# MCU_RGB.net
KiCad netlist of a schematic drawn in Altium Designer
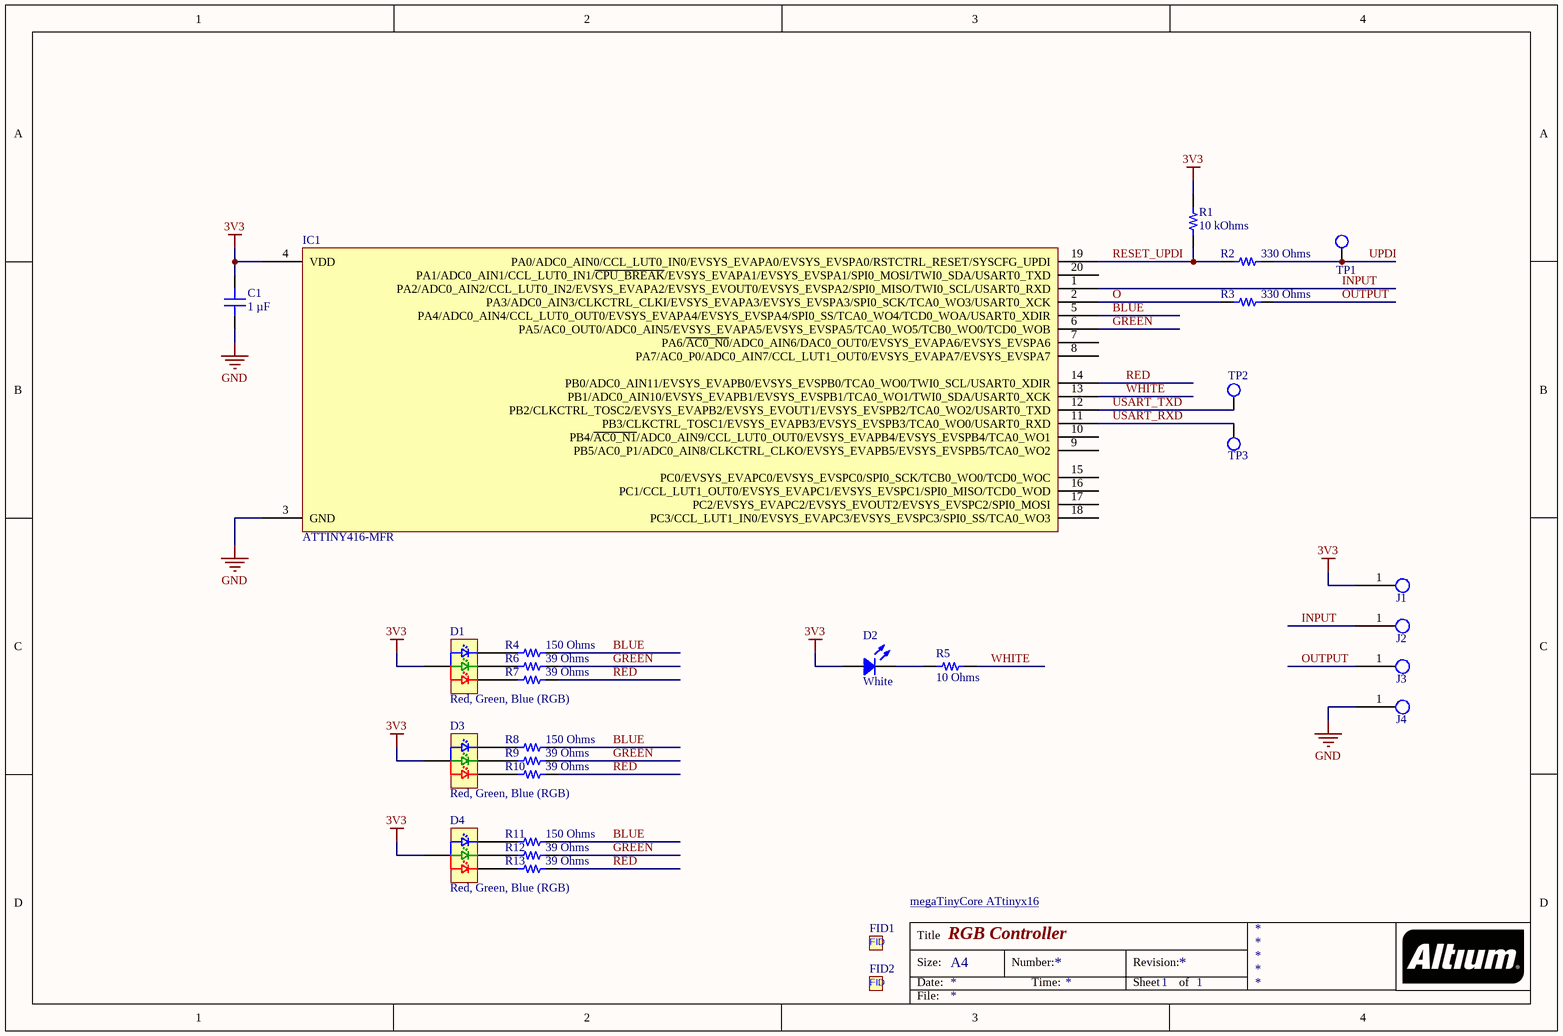
[diagram p0: MCU RGB.SchDoc]

(export (version "E")
  (design (tool "Eeschema 10.0.6"))
  (components
    (comp (ref "C1")
      (value "1 µF")
      (footprint "CAP 0603_1608")
      (description "CAP CER 1UF 25V X7R 0603")
      (fields
        (field (name "PART NUMBER") "GCM188R71E105KA64D")
        (field (name "MANUFACTURER") "Murata Electronics")
      )
      (libsource (lib "altiumlibrary.com") (part "Capacitor"))
    )
    (comp (ref "D1")
      (value "Red, Green, Blue (RGB)")
      (footprint "Harvatek B38G3RGB-10D0003H2U1930")
      (description "LED RGB MIXED WHITE ( 1.6(L)X1.6")
      (fields
        (field (name "PART NUMBER") "B38G3RGB-10D0003H2U1930")
        (field (name "MANUFACTURER") "Harvatek Corporation")
      )
      (libsource (lib "altiumlibrary.com") (part "Harvatek B38G3RGB-10D0003H2U1930"))
    )
    (comp (ref "D2")
      (value "White")
      (footprint "LED 0603_1608")
      (description "1.6(L)X0.8(W)X0.4(H) MM WHITE LE")
      (fields
        (field (name "PART NUMBER") "B1931TW--20P000314U1930")
        (field (name "MANUFACTURER") "Harvatek Corporation")
      )
      (libsource (lib "altiumlibrary.com") (part "LED"))
    )
    (comp (ref "D3")
      (value "Red, Green, Blue (RGB)")
      (footprint "Harvatek B38G3RGB-10D0003H2U1930")
      (description "LED RGB MIXED WHITE ( 1.6(L)X1.6")
      (fields
        (field (name "PART NUMBER") "B38G3RGB-10D0003H2U1930")
        (field (name "MANUFACTURER") "Harvatek Corporation")
      )
      (libsource (lib "altiumlibrary.com") (part "Harvatek B38G3RGB-10D0003H2U1930"))
    )
    (comp (ref "D4")
      (value "Red, Green, Blue (RGB)")
      (footprint "Harvatek B38G3RGB-10D0003H2U1930")
      (description "LED RGB MIXED WHITE ( 1.6(L)X1.6")
      (fields
        (field (name "PART NUMBER") "B38G3RGB-10D0003H2U1930")
        (field (name "MANUFACTURER") "Harvatek Corporation")
      )
      (libsource (lib "altiumlibrary.com") (part "Harvatek B38G3RGB-10D0003H2U1930"))
    )
    (comp (ref "FID1")
      (value "Fiducial")
      (footprint "Fiducial-1mm")
      (libsource (lib "Original Circuit") (part "Fiducial"))
    )
    (comp (ref "FID2")
      (value "Fiducial")
      (footprint "Fiducial-1mm")
      (libsource (lib "Original Circuit") (part "Fiducial"))
    )
    (comp (ref "IC1")
      (value "ATTINY416-MFR")
      (footprint "MICROCHIP VQFN-20 3X3 REB")
      (description "IC MCU 8BIT 4KB FLASH 20VQFN")
      (fields (field (name "MANUFACTURER") "Microchip Technology"))
      (libsource (lib "altiumlibrary.com") (part "MICROCHIP ATTINY416-MFR VQFN20"))
    )
    (comp (ref "J1")
      (value "e-tex pad")
      (footprint "MFR PARTNO")
      (libsource (lib "e-tex pad") (part "e-tex pad"))
    )
    (comp (ref "J2")
      (value "e-tex pad")
      (footprint "MFR PARTNO")
      (libsource (lib "e-tex pad") (part "e-tex pad"))
    )
    (comp (ref "J3")
      (value "e-tex pad")
      (footprint "MFR PARTNO")
      (libsource (lib "e-tex pad") (part "e-tex pad"))
    )
    (comp (ref "J4")
      (value "e-tex pad")
      (footprint "MFR PARTNO")
      (libsource (lib "e-tex pad") (part "e-tex pad"))
    )
    (comp (ref "R1")
      (value "10 kOhms")
      (footprint "RES 0201_0603")
      (description "RES SMD 10K OHM 5% 1/20W 0201")
      (fields (field (name "PART NUMBER") "CR0201-JW-103GLF") (field (name "MANUFACTURER") "Bourns Inc."))
      (libsource (lib "altiumlibrary.com") (part "Resistor"))
    )
    (comp (ref "R2")
      (value "330 Ohms")
      (footprint "RES 0201_0603")
      (description "RES 330 OHM 1% 1/20W 0201")
      (fields
        (field (name "PART NUMBER") "WR02X3300FAL")
        (field (name "MANUFACTURER") "Walsin Technology Corporation")
      )
      (libsource (lib "altiumlibrary.com") (part "Resistor"))
    )
    (comp (ref "R3")
      (value "330 Ohms")
      (footprint "RES 0201_0603")
      (description "RES 330 OHM 1% 1/20W 0201")
      (fields
        (field (name "PART NUMBER") "WR02X3300FAL")
        (field (name "MANUFACTURER") "Walsin Technology Corporation")
      )
      (libsource (lib "altiumlibrary.com") (part "Resistor"))
    )
    (comp (ref "R4")
      (value "150 Ohms")
      (footprint "RES 0201_0603")
      (description "RES 150 OHM 5% 1/20W 0201")
      (fields
        (field (name "PART NUMBER") "WR02X151 JAL")
        (field (name "MANUFACTURER") "Walsin Technology Corporation")
      )
      (libsource (lib "altiumlibrary.com") (part "Resistor"))
    )
    (comp (ref "R5")
      (value "10 Ohms")
      (footprint "RES 0201_0603")
      (description "RES 10 OHM 1% 1/20W 0201")
      (fields
        (field (name "PART NUMBER") "WR02X10R0FAL")
        (field (name "MANUFACTURER") "Walsin Technology Corporation")
      )
      (libsource (lib "altiumlibrary.com") (part "Resistor"))
    )
    (comp (ref "R6")
      (value "39 Ohms")
      (footprint "RES 0201_0603")
      (description "RES SMD 39 OHM 5% 1/20W 0201")
      (fields (field (name "PART NUMBER") "CR0201-JW-390GLF") (field (name "MANUFACTURER") "Bourns Inc."))
      (libsource (lib "altiumlibrary.com") (part "Resistor"))
    )
    (comp (ref "R7")
      (value "39 Ohms")
      (footprint "RES 0201_0603")
      (description "RES SMD 39 OHM 5% 1/20W 0201")
      (fields (field (name "PART NUMBER") "CR0201-JW-390GLF") (field (name "MANUFACTURER") "Bourns Inc."))
      (libsource (lib "altiumlibrary.com") (part "Resistor"))
    )
    (comp (ref "R8")
      (value "150 Ohms")
      (footprint "RES 0201_0603")
      (description "RES 150 OHM 5% 1/20W 0201")
      (fields
        (field (name "PART NUMBER") "WR02X151 JAL")
        (field (name "MANUFACTURER") "Walsin Technology Corporation")
      )
      (libsource (lib "altiumlibrary.com") (part "Resistor"))
    )
    (comp (ref "R9")
      (value "39 Ohms")
      (footprint "RES 0201_0603")
      (description "RES SMD 39 OHM 5% 1/20W 0201")
      (fields (field (name "PART NUMBER") "CR0201-JW-390GLF") (field (name "MANUFACTURER") "Bourns Inc."))
      (libsource (lib "altiumlibrary.com") (part "Resistor"))
    )
    (comp (ref "R10")
      (value "39 Ohms")
      (footprint "RES 0201_0603")
      (description "RES SMD 39 OHM 5% 1/20W 0201")
      (fields (field (name "PART NUMBER") "CR0201-JW-390GLF") (field (name "MANUFACTURER") "Bourns Inc."))
      (libsource (lib "altiumlibrary.com") (part "Resistor"))
    )
    (comp (ref "R11")
      (value "150 Ohms")
      (footprint "RES 0201_0603")
      (description "RES 150 OHM 5% 1/20W 0201")
      (fields
        (field (name "PART NUMBER") "WR02X151 JAL")
        (field (name "MANUFACTURER") "Walsin Technology Corporation")
      )
      (libsource (lib "altiumlibrary.com") (part "Resistor"))
    )
    (comp (ref "R12")
      (value "39 Ohms")
      (footprint "RES 0201_0603")
      (description "RES SMD 39 OHM 5% 1/20W 0201")
      (fields (field (name "PART NUMBER") "CR0201-JW-390GLF") (field (name "MANUFACTURER") "Bourns Inc."))
      (libsource (lib "altiumlibrary.com") (part "Resistor"))
    )
    (comp (ref "R13")
      (value "39 Ohms")
      (footprint "RES 0201_0603")
      (description "RES SMD 39 OHM 5% 1/20W 0201")
      (fields (field (name "PART NUMBER") "CR0201-JW-390GLF") (field (name "MANUFACTURER") "Bourns Inc."))
      (libsource (lib "altiumlibrary.com") (part "Resistor"))
    )
    (comp (ref "TP1")
      (value "Test Point")
      (footprint "TestPoint-1.5mm")
      (libsource (lib "Original Circuit") (part "Test Point"))
    )
    (comp (ref "TP2")
      (value "Test Point")
      (footprint "TestPoint-1.5mm")
      (libsource (lib "Original Circuit") (part "Test Point"))
    )
    (comp (ref "TP3")
      (value "Test Point")
      (footprint "TestPoint-1.5mm")
      (libsource (lib "Original Circuit") (part "Test Point"))
    )
  )
  (nets
    (net (code "1") (name "/BLUE") (class "Default")
      (node (ref "IC1") (pin "5") (pinfunction "PA4/ADC0_AIN4/CCL_LUT0_OUT0/EVSYS_EVAPA4/EVSYS_EVSPA4/SPI0_SS/TCA0_WO4/TCD0_WOA/USART0_XDIR_5") (pintype "passive"))
      (node (ref "R11") (pin "2") (pinfunction "2_2") (pintype "passive"))
      (node (ref "R4") (pin "2") (pinfunction "2_2") (pintype "passive"))
      (node (ref "R8") (pin "2") (pinfunction "2_2") (pintype "passive"))
    )
    (net (code "2") (name "/GREEN") (class "Default")
      (node (ref "IC1") (pin "6") (pinfunction "PA5/AC0_OUT0/ADC0_AIN5/EVSYS_EVAPA5/EVSYS_EVSPA5/TCA0_WO5/TCB0_WO0/TCD0_WOB_6") (pintype "passive"))
      (node (ref "R12") (pin "2") (pinfunction "2_2") (pintype "passive"))
      (node (ref "R6") (pin "2") (pinfunction "2_2") (pintype "passive"))
      (node (ref "R9") (pin "2") (pinfunction "2_2") (pintype "passive"))
    )
    (net (code "3") (name "/INPUT") (class "Default")
      (node (ref "IC1") (pin "1") (pinfunction "PA2/ADC0_AIN2/CCL_LUT0_IN2/EVSYS_EVAPA2/EVSYS_EVOUT0/EVSYS_EVSPA2/SPI0_MISO/TWI0_SCL/USART0_RXD_1") (pintype "passive"))
      (node (ref "J2") (pin "1") (pinfunction "ETEXTILE_1") (pintype "passive"))
    )
    (net (code "4") (name "/O") (class "Default")
      (node (ref "IC1") (pin "2") (pinfunction "PA3/ADC0_AIN3/CLKCTRL_CLKI/EVSYS_EVAPA3/EVSYS_EVSPA3/SPI0_SCK/TCA0_WO3/USART0_XCK_2") (pintype "passive"))
      (node (ref "R3") (pin "1") (pinfunction "1_1") (pintype "passive"))
    )
    (net (code "5") (name "/OUTPUT") (class "Default")
      (node (ref "J3") (pin "1") (pinfunction "ETEXTILE_1") (pintype "passive"))
      (node (ref "R3") (pin "2") (pinfunction "2_2") (pintype "passive"))
    )
    (net (code "6") (name "/RED") (class "Default")
      (node (ref "IC1") (pin "14") (pinfunction "PB0/ADC0_AIN11/EVSYS_EVAPB0/EVSYS_EVSPB0/TCA0_WO0/TWI0_SCL/USART0_XDIR_14") (pintype "passive"))
      (node (ref "R10") (pin "2") (pinfunction "2_2") (pintype "passive"))
      (node (ref "R13") (pin "2") (pinfunction "2_2") (pintype "passive"))
      (node (ref "R7") (pin "2") (pinfunction "2_2") (pintype "passive"))
    )
    (net (code "7") (name "/RESET_UPDI") (class "Default")
      (node (ref "IC1") (pin "19") (pinfunction "PA0/ADC0_AIN0/CCL_LUT0_IN0/EVSYS_EVAPA0/EVSYS_EVSPA0/RSTCTRL_RESET/SYSCFG_UPDI_19") (pintype "passive"))
      (node (ref "R1") (pin "1") (pinfunction "1_1") (pintype "passive"))
      (node (ref "R2") (pin "1") (pinfunction "1_1") (pintype "passive"))
    )
    (net (code "8") (name "/UPDI") (class "Default")
      (node (ref "R2") (pin "2") (pinfunction "2_2") (pintype "passive"))
      (node (ref "TP1") (pin "1") (pinfunction "TP_1") (pintype "passive"))
    )
    (net (code "9") (name "/USART_RXD") (class "Default")
      (node (ref "IC1") (pin "11") (pinfunction "PB3/CLKCTRL_TOSC1/EVSYS_EVAPB3/EVSYS_EVSPB3/TCA0_WO0/USART0_RXD_11") (pintype "passive"))
      (node (ref "TP3") (pin "1") (pinfunction "TP_1") (pintype "passive"))
    )
    (net (code "10") (name "/USART_TXD") (class "Default")
      (node (ref "IC1") (pin "12") (pinfunction "PB2/CLKCTRL_TOSC2/EVSYS_EVAPB2/EVSYS_EVOUT1/EVSYS_EVSPB2/TCA0_WO2/USART0_TXD_12") (pintype "passive"))
      (node (ref "TP2") (pin "1") (pinfunction "TP_1") (pintype "passive"))
    )
    (net (code "11") (name "/WHITE") (class "Default")
      (node (ref "IC1") (pin "13") (pinfunction "PB1/ADC0_AIN10/EVSYS_EVAPB1/EVSYS_EVSPB1/TCA0_WO1/TWI0_SDA/USART0_XCK_13") (pintype "passive"))
      (node (ref "R5") (pin "2") (pinfunction "2_2") (pintype "passive"))
    )
    (net (code "12") (name "3V3") (class "Default")
      (node (ref "C1") (pin "2") (pinfunction "2_2") (pintype "passive"))
      (node (ref "D1") (pin "3") (pinfunction "ANODE_3") (pintype "passive"))
      (node (ref "D2") (pin "1") (pinfunction "1_1") (pintype "passive"))
      (node (ref "D3") (pin "3") (pinfunction "ANODE_3") (pintype "passive"))
      (node (ref "D4") (pin "3") (pinfunction "ANODE_3") (pintype "passive"))
      (node (ref "IC1") (pin "4") (pinfunction "VDD_4") (pintype "passive"))
      (node (ref "J1") (pin "1") (pinfunction "ETEXTILE_1") (pintype "passive"))
      (node (ref "R1") (pin "2") (pinfunction "2_2") (pintype "passive"))
    )
    (net (code "13") (name "GND") (class "Default")
      (node (ref "C1") (pin "1") (pinfunction "1_1") (pintype "passive"))
      (node (ref "IC1") (pin "3") (pinfunction "GND_3") (pintype "passive"))
      (node (ref "J4") (pin "1") (pinfunction "ETEXTILE_1") (pintype "passive"))
    )
    (net (code "14") (name "Net-(D1-BLUE)") (class "Default")
      (node (ref "D1") (pin "2") (pinfunction "BLUE_2") (pintype "passive"))
      (node (ref "R4") (pin "1") (pinfunction "1_1") (pintype "passive"))
    )
    (net (code "15") (name "Net-(D1-GREEN)") (class "Default")
      (node (ref "D1") (pin "1") (pinfunction "GREEN_1") (pintype "passive"))
      (node (ref "R6") (pin "1") (pinfunction "1_1") (pintype "passive"))
    )
    (net (code "16") (name "Net-(D1-RED)") (class "Default")
      (node (ref "D1") (pin "4") (pinfunction "RED_4") (pintype "passive"))
      (node (ref "R7") (pin "1") (pinfunction "1_1") (pintype "passive"))
    )
    (net (code "17") (name "Net-(D2-Pad2)") (class "Default")
      (node (ref "D2") (pin "2") (pinfunction "2_2") (pintype "passive"))
      (node (ref "R5") (pin "1") (pinfunction "1_1") (pintype "passive"))
    )
    (net (code "18") (name "Net-(D3-BLUE)") (class "Default")
      (node (ref "D3") (pin "2") (pinfunction "BLUE_2") (pintype "passive"))
      (node (ref "R8") (pin "1") (pinfunction "1_1") (pintype "passive"))
    )
    (net (code "19") (name "Net-(D3-GREEN)") (class "Default")
      (node (ref "D3") (pin "1") (pinfunction "GREEN_1") (pintype "passive"))
      (node (ref "R9") (pin "1") (pinfunction "1_1") (pintype "passive"))
    )
    (net (code "20") (name "Net-(D3-RED)") (class "Default")
      (node (ref "D3") (pin "4") (pinfunction "RED_4") (pintype "passive"))
      (node (ref "R10") (pin "1") (pinfunction "1_1") (pintype "passive"))
    )
    (net (code "21") (name "Net-(D4-BLUE)") (class "Default")
      (node (ref "D4") (pin "2") (pinfunction "BLUE_2") (pintype "passive"))
      (node (ref "R11") (pin "1") (pinfunction "1_1") (pintype "passive"))
    )
    (net (code "22") (name "Net-(D4-GREEN)") (class "Default")
      (node (ref "D4") (pin "1") (pinfunction "GREEN_1") (pintype "passive"))
      (node (ref "R12") (pin "1") (pinfunction "1_1") (pintype "passive"))
    )
    (net (code "23") (name "Net-(D4-RED)") (class "Default")
      (node (ref "D4") (pin "4") (pinfunction "RED_4") (pintype "passive"))
      (node (ref "R13") (pin "1") (pinfunction "1_1") (pintype "passive"))
    )
    (net (code "24") (name "unconnected-(IC1-PA1{slash}ADC0_AIN1{slash}CCL_LUT0_IN1{slash}~{CPU_BREAK}{slash}EVSYS_EVAPA1{slash}EVSYS_EVSPA1{slash}SPI0_MOSI{slash}TWI0_SDA{slash}USART0_TXD-Pad20)") (class "Default")
      (node (ref "IC1") (pin "20") (pinfunction "PA1/ADC0_AIN1/CCL_LUT0_IN1/~{CPU_BREAK}/EVSYS_EVAPA1/EVSYS_EVSPA1/SPI0_MOSI/TWI0_SDA/USART0_TXD_20") (pintype "passive"))
    )
    (net (code "25") (name "unconnected-(IC1-PA6{slash}~{AC0_N0}{slash}ADC0_AIN6{slash}DAC0_OUT0{slash}EVSYS_EVAPA6{slash}EVSYS_EVSPA6-Pad7)") (class "Default")
      (node (ref "IC1") (pin "7") (pinfunction "PA6/~{AC0_N0}/ADC0_AIN6/DAC0_OUT0/EVSYS_EVAPA6/EVSYS_EVSPA6_7") (pintype "passive"))
    )
    (net (code "26") (name "unconnected-(IC1-PA7{slash}AC0_P0{slash}ADC0_AIN7{slash}CCL_LUT1_OUT0{slash}EVSYS_EVAPA7{slash}EVSYS_EVSPA7-Pad8)") (class "Default")
      (node (ref "IC1") (pin "8") (pinfunction "PA7/AC0_P0/ADC0_AIN7/CCL_LUT1_OUT0/EVSYS_EVAPA7/EVSYS_EVSPA7_8") (pintype "passive"))
    )
    (net (code "27") (name "unconnected-(IC1-PB4{slash}~{AC0_N1}{slash}ADC0_AIN9{slash}CCL_LUT0_OUT0{slash}EVSYS_EVAPB4{slash}EVSYS_EVSPB4{slash}TCA0_WO1-Pad10)") (class "Default")
      (node (ref "IC1") (pin "10") (pinfunction "PB4/~{AC0_N1}/ADC0_AIN9/CCL_LUT0_OUT0/EVSYS_EVAPB4/EVSYS_EVSPB4/TCA0_WO1_10") (pintype "passive"))
    )
    (net (code "28") (name "unconnected-(IC1-PB5{slash}AC0_P1{slash}ADC0_AIN8{slash}CLKCTRL_CLKO{slash}EVSYS_EVAPB5{slash}EVSYS_EVSPB5{slash}TCA0_WO2-Pad9)") (class "Default")
      (node (ref "IC1") (pin "9") (pinfunction "PB5/AC0_P1/ADC0_AIN8/CLKCTRL_CLKO/EVSYS_EVAPB5/EVSYS_EVSPB5/TCA0_WO2_9") (pintype "passive"))
    )
    (net (code "29") (name "unconnected-(IC1-PC0{slash}EVSYS_EVAPC0{slash}EVSYS_EVSPC0{slash}SPI0_SCK{slash}TCB0_WO0{slash}TCD0_WOC-Pad15)") (class "Default")
      (node (ref "IC1") (pin "15") (pinfunction "PC0/EVSYS_EVAPC0/EVSYS_EVSPC0/SPI0_SCK/TCB0_WO0/TCD0_WOC_15") (pintype "passive"))
    )
    (net (code "30") (name "unconnected-(IC1-PC1{slash}CCL_LUT1_OUT0{slash}EVSYS_EVAPC1{slash}EVSYS_EVSPC1{slash}SPI0_MISO{slash}TCD0_WOD-Pad16)") (class "Default")
      (node (ref "IC1") (pin "16") (pinfunction "PC1/CCL_LUT1_OUT0/EVSYS_EVAPC1/EVSYS_EVSPC1/SPI0_MISO/TCD0_WOD_16") (pintype "passive"))
    )
    (net (code "31") (name "unconnected-(IC1-PC2{slash}EVSYS_EVAPC2{slash}EVSYS_EVOUT2{slash}EVSYS_EVSPC2{slash}SPI0_MOSI-Pad17)") (class "Default")
      (node (ref "IC1") (pin "17") (pinfunction "PC2/EVSYS_EVAPC2/EVSYS_EVOUT2/EVSYS_EVSPC2/SPI0_MOSI_17") (pintype "passive"))
    )
    (net (code "32") (name "unconnected-(IC1-PC3{slash}CCL_LUT1_IN0{slash}EVSYS_EVAPC3{slash}EVSYS_EVSPC3{slash}SPI0_SS{slash}TCA0_WO3-Pad18)") (class "Default")
      (node (ref "IC1") (pin "18") (pinfunction "PC3/CCL_LUT1_IN0/EVSYS_EVAPC3/EVSYS_EVSPC3/SPI0_SS/TCA0_WO3_18") (pintype "passive"))
    )
  )
)
